# Fuse.net
KiCad netlist of a schematic drawn in Altium Designer
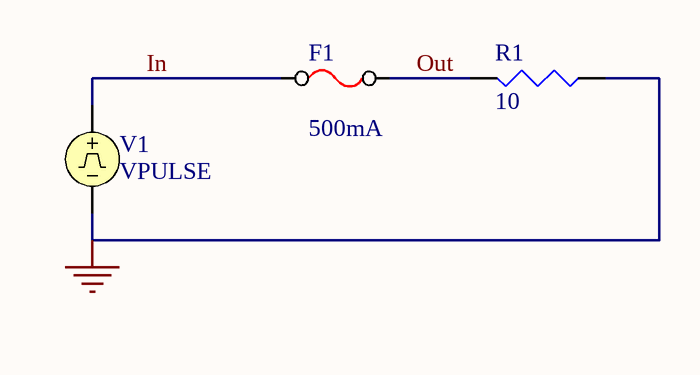
[diagram p0: Fuse.schdoc]

(export (version "E")
  (design (tool "Eeschema 10.0.6"))
  (components
    (comp (ref "F1")
      (value "500mA")
      (description "Fuse")
      (fields (field (name "CURRENT") "500mA"))
      (libsource (lib "*") (part "FUSE"))
    )
    (comp (ref "R1") (value "10") (description "Resistor") (libsource (lib "*") (part "RES")))
    (comp (ref "V1")
      (value "VPULSE")
      (description "Pulse Voltage Source")
      (libsource (lib "*") (part "VPULSE"))
    )
  )
  (nets
    (net (code "1") (name "/In") (class "Default")
      (node (ref "F1") (pin "1") (pinfunction "1_1") (pintype "passive"))
      (node (ref "V1") (pin "1") (pinfunction "1_1") (pintype "passive"))
    )
    (net (code "2") (name "/Out") (class "Default")
      (node (ref "F1") (pin "2") (pinfunction "2_2") (pintype "passive"))
      (node (ref "R1") (pin "1") (pinfunction "TOP_1") (pintype "passive"))
    )
    (net (code "3") (name "GND") (class "Default")
      (node (ref "R1") (pin "2") (pinfunction "BOT_2") (pintype "passive"))
      (node (ref "V1") (pin "2") (pinfunction "2_2") (pintype "passive"))
    )
  )
)
